# motor_42.net
KiCad netlist of a schematic drawn in Altium Designer
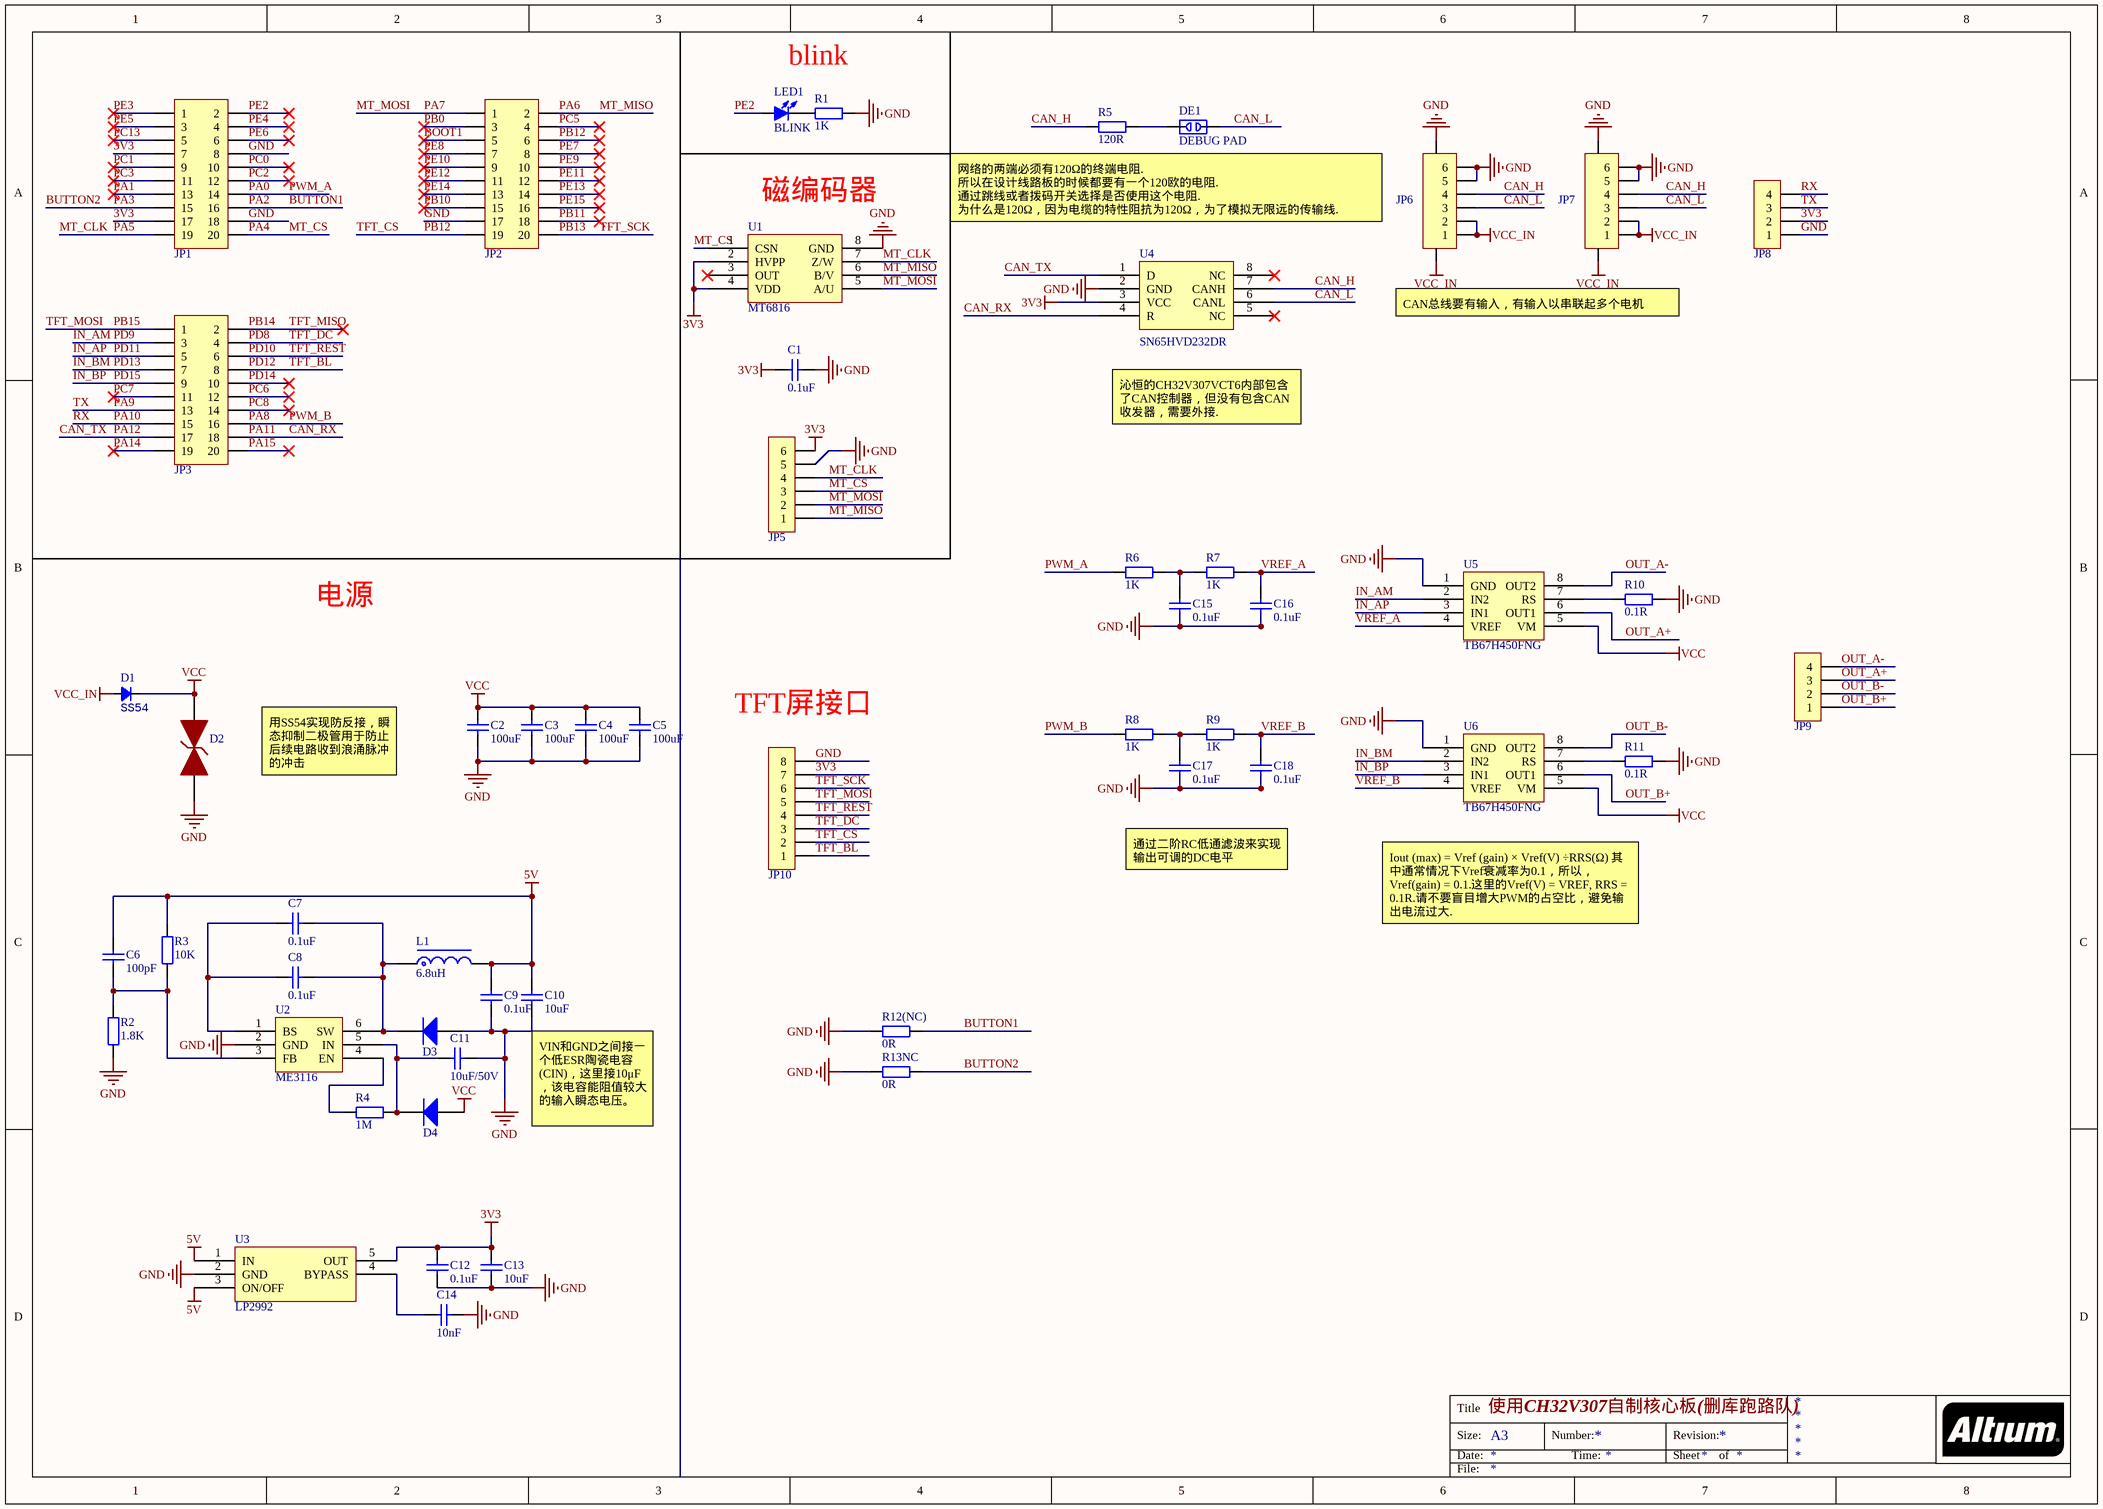
[diagram p0: motor_42.SchDoc]

(export (version "E")
  (design (tool "Eeschema 10.0.6"))
  (components
    (comp (ref "C1")
      (value "0.1uF")
      (footprint "C0805_L")
      (description "贴片电容/MLCC电容")
      (libsource (lib "0.1 - 电阻-电容-电感-晶振-晶体-磁珠-电位器-法拉电容-馈通电容") (part "C"))
    )
    (comp (ref "C2")
      (value "100uF")
      (footprint "C1206_L")
      (description "贴片电容/MLCC电容")
      (libsource (lib "0.1 - 电阻-电容-电感-晶振-晶体-磁珠-电位器-法拉电容-馈通电容") (part "C"))
    )
    (comp (ref "C3")
      (value "100uF")
      (footprint "C1206_L")
      (description "贴片电容/MLCC电容")
      (libsource (lib "0.1 - 电阻-电容-电感-晶振-晶体-磁珠-电位器-法拉电容-馈通电容") (part "C"))
    )
    (comp (ref "C4")
      (value "100uF")
      (footprint "C1206_L")
      (description "贴片电容/MLCC电容")
      (libsource (lib "0.1 - 电阻-电容-电感-晶振-晶体-磁珠-电位器-法拉电容-馈通电容") (part "C"))
    )
    (comp (ref "C5")
      (value "100uF")
      (footprint "C1206_L")
      (description "贴片电容/MLCC电容")
      (libsource (lib "0.1 - 电阻-电容-电感-晶振-晶体-磁珠-电位器-法拉电容-馈通电容") (part "C"))
    )
    (comp (ref "C6")
      (value "100pF")
      (footprint "C0402_L")
      (description "贴片电容/MLCC电容")
      (libsource (lib "0.1 - 电阻-电容-电感-晶振-晶体-磁珠-电位器-法拉电容-馈通电容") (part "C"))
    )
    (comp (ref "C7")
      (value "0.1uF")
      (footprint "C0402_L")
      (description "贴片电容/MLCC电容")
      (libsource (lib "0.1 - 电阻-电容-电感-晶振-晶体-磁珠-电位器-法拉电容-馈通电容") (part "C"))
    )
    (comp (ref "C8")
      (value "0.1uF")
      (footprint "C0402_L")
      (description "贴片电容/MLCC电容")
      (libsource (lib "0.1 - 电阻-电容-电感-晶振-晶体-磁珠-电位器-法拉电容-馈通电容") (part "C"))
    )
    (comp (ref "C9")
      (value "0.1uF")
      (footprint "C0402_L")
      (description "贴片电容/MLCC电容")
      (libsource (lib "0.1 - 电阻-电容-电感-晶振-晶体-磁珠-电位器-法拉电容-馈通电容") (part "C"))
    )
    (comp (ref "C10")
      (value "10uF")
      (footprint "C0402_L")
      (description "贴片电容/MLCC电容")
      (libsource (lib "0.1 - 电阻-电容-电感-晶振-晶体-磁珠-电位器-法拉电容-馈通电容") (part "C"))
    )
    (comp (ref "C11")
      (value "10uF/50V")
      (footprint "C0603_L")
      (description "陶瓷电容")
      (libsource (lib "0.1 - 电阻-电容-电感-晶振-晶体-磁珠-电位器-法拉电容-馈通电容") (part "C"))
    )
    (comp (ref "C12")
      (value "0.1uF")
      (footprint "C0402_L")
      (description "贴片电容/MLCC电容")
      (libsource (lib "0.1 - 电阻-电容-电感-晶振-晶体-磁珠-电位器-法拉电容-馈通电容") (part "C"))
    )
    (comp (ref "C13")
      (value "10uF")
      (footprint "C0402_L")
      (description "贴片电容/MLCC电容")
      (libsource (lib "0.1 - 电阻-电容-电感-晶振-晶体-磁珠-电位器-法拉电容-馈通电容") (part "C"))
    )
    (comp (ref "C14")
      (value "10nF")
      (footprint "C0402_L")
      (description "贴片电容/MLCC电容")
      (libsource (lib "0.1 - 电阻-电容-电感-晶振-晶体-磁珠-电位器-法拉电容-馈通电容") (part "C"))
    )
    (comp (ref "C15")
      (value "0.1uF")
      (footprint "C0402_L")
      (description "贴片电容/MLCC电容")
      (libsource (lib "0.1 - 电阻-电容-电感-晶振-晶体-磁珠-电位器-法拉电容-馈通电容") (part "C"))
    )
    (comp (ref "C16")
      (value "0.1uF")
      (footprint "C0402_L")
      (description "贴片电容/MLCC电容")
      (libsource (lib "0.1 - 电阻-电容-电感-晶振-晶体-磁珠-电位器-法拉电容-馈通电容") (part "C"))
    )
    (comp (ref "C17")
      (value "0.1uF")
      (footprint "C0402_L")
      (description "贴片电容/MLCC电容")
      (libsource (lib "0.1 - 电阻-电容-电感-晶振-晶体-磁珠-电位器-法拉电容-馈通电容") (part "C"))
    )
    (comp (ref "C18")
      (value "0.1uF")
      (footprint "C0402_L")
      (description "贴片电容/MLCC电容")
      (libsource (lib "0.1 - 电阻-电容-电感-晶振-晶体-磁珠-电位器-法拉电容-馈通电容") (part "C"))
    )
    (comp (ref "D1")
      (value "SS54")
      (footprint "SMA")
      (description "Diode")
      (libsource (lib "KitSprout") (part "Diode_SMA"))
    )
    (comp (ref "D2") (value "SMBJ28CA") (footprint "SMB") (libsource (lib "MyPcbLib") (part "SMBJ28CA")))
    (comp (ref "D3")
      (value "二极管-5819W")
      (footprint "SOD-323")
      (description "40V")
      (libsource (lib "0.2 - 二极管-TVS-ESD-整流桥-放电管") (part "二极管-5819W"))
    )
    (comp (ref "D4")
      (value "二极管-5819W")
      (footprint "SOD-323")
      (description "40V")
      (libsource (lib "0.2 - 二极管-TVS-ESD-整流桥-放电管") (part "二极管-5819W"))
    )
    (comp (ref "DE1")
      (value "DEBUG PAD")
      (footprint "DEBUG_A")
      (description "调试断点焊盘")
      (libsource (lib "0.5 - 按键_开关_蜂鸣器_保险丝_电池_测试点_Mark点_铜柱") (part "DEBUG"))
    )
    (comp (ref "JP1")
      (value "Header 2X10")
      (footprint "HDR2.54-LI-2x10P")
      (description "10*2P接插件")
      (libsource (lib "5.5 - 2.54mm连接器(KF2EDGK_XH2.54_2.54排针排母)") (part "Header 10X2"))
    )
    (comp (ref "JP2")
      (value "Header 2X10")
      (footprint "HDR2.54-LI-2x10P")
      (description "10*2P接插件")
      (libsource (lib "5.5 - 2.54mm连接器(KF2EDGK_XH2.54_2.54排针排母)") (part "Header 10X2"))
    )
    (comp (ref "JP3")
      (value "Header 2X10")
      (footprint "HDR2.54-LI-2x10P")
      (description "10*2P接插件")
      (libsource (lib "5.5 - 2.54mm连接器(KF2EDGK_XH2.54_2.54排针排母)") (part "Header 10X2"))
    )
    (comp (ref "JP5")
      (value "HDR-1X6")
      (footprint "HDR2.54-LI-6P")
      (description "6P接插件")
      (libsource (lib "5.5 - 2.54mm连接器(KF2EDGK_XH2.54_2.54排针排母)") (part "Header 6"))
    )
    (comp (ref "JP6")
      (value "HDR-1X6")
      (footprint "SH1.0-WT-6P")
      (description "6P连接器")
      (libsource (lib "5.0 - 1.00mm连接器(FPC1.0_SH1.0_1.0排针排母)") (part "Header 6"))
    )
    (comp (ref "JP7")
      (value "HDR-1X6")
      (footprint "SH1.0-WT-6P")
      (description "6P连接器")
      (libsource (lib "5.0 - 1.00mm连接器(FPC1.0_SH1.0_1.0排针排母)") (part "Header 6"))
    )
    (comp (ref "JP8")
      (value "HDR-1X4")
      (footprint "HDR2.54-LI-4P")
      (description "4P接插件")
      (libsource (lib "5.5 - 2.54mm连接器(KF2EDGK_XH2.54_2.54排针排母)") (part "Header 4"))
    )
    (comp (ref "JP9")
      (value "HDR-1X4")
      (footprint "XH2.54-LI-4P")
      (description "4P接插件")
      (libsource (lib "5.5 - 2.54mm连接器(KF2EDGK_XH2.54_2.54排针排母)") (part "Header 4"))
    )
    (comp (ref "JP10")
      (value "HDR-1X8")
      (footprint "HDR2.54-M-LI-8P")
      (description "8P接插件")
      (libsource (lib "5.5 - 2.54mm连接器(KF2EDGK_XH2.54_2.54排针排母)") (part "Header 8"))
    )
    (comp (ref "L1")
      (value "6.8uH")
      (footprint "L-SMD-0420")
      (description "一体成型电感")
      (libsource (lib "0.1 - 电阻-电容-电感-晶振-晶体-磁珠-电位器-法拉电容-馈通电容") (part "L-Molding Choke"))
    )
    (comp (ref "LED1")
      (value "BLINK")
      (footprint "LED0805_G")
      (description "贴片LED")
      (libsource (lib "0.3 - LED发光二极管-IR二极管_接收管-光耦") (part "LED-SMD"))
    )
    (comp (ref "R1")
      (value "1K")
      (footprint "R0402_L")
      (description "贴片电阻")
      (libsource (lib "0.1 - 电阻-电容-电感-晶振-晶体-磁珠-电位器-法拉电容-馈通电容") (part "R"))
    )
    (comp (ref "R2")
      (value "1.8K")
      (footprint "R0402_L")
      (description "贴片电阻")
      (libsource (lib "0.1 - 电阻-电容-电感-晶振-晶体-磁珠-电位器-法拉电容-馈通电容") (part "R"))
    )
    (comp (ref "R3")
      (value "10K")
      (footprint "R0402_L")
      (description "贴片电阻")
      (libsource (lib "0.1 - 电阻-电容-电感-晶振-晶体-磁珠-电位器-法拉电容-馈通电容") (part "R"))
    )
    (comp (ref "R4")
      (value "1M")
      (footprint "R0402_L")
      (description "贴片电阻")
      (libsource (lib "0.1 - 电阻-电容-电感-晶振-晶体-磁珠-电位器-法拉电容-馈通电容") (part "R"))
    )
    (comp (ref "R5")
      (value "120R")
      (footprint "R0402_L")
      (description "贴片电阻")
      (libsource (lib "0.1 - 电阻-电容-电感-晶振-晶体-磁珠-电位器-法拉电容-馈通电容") (part "R"))
    )
    (comp (ref "R6")
      (value "1K")
      (footprint "R0402_L")
      (description "贴片电阻")
      (libsource (lib "0.1 - 电阻-电容-电感-晶振-晶体-磁珠-电位器-法拉电容-馈通电容") (part "R"))
    )
    (comp (ref "R7")
      (value "1K")
      (footprint "R0402_L")
      (description "贴片电阻")
      (libsource (lib "0.1 - 电阻-电容-电感-晶振-晶体-磁珠-电位器-法拉电容-馈通电容") (part "R"))
    )
    (comp (ref "R8")
      (value "1K")
      (footprint "R0402_L")
      (description "贴片电阻")
      (libsource (lib "0.1 - 电阻-电容-电感-晶振-晶体-磁珠-电位器-法拉电容-馈通电容") (part "R"))
    )
    (comp (ref "R9")
      (value "1K")
      (footprint "R0402_L")
      (description "贴片电阻")
      (libsource (lib "0.1 - 电阻-电容-电感-晶振-晶体-磁珠-电位器-法拉电容-馈通电容") (part "R"))
    )
    (comp (ref "R10")
      (value "0.1R")
      (footprint "R1206_L")
      (description "贴片电阻")
      (libsource (lib "0.1 - 电阻-电容-电感-晶振-晶体-磁珠-电位器-法拉电容-馈通电容") (part "R"))
    )
    (comp (ref "R11")
      (value "0.1R")
      (footprint "R1206_L")
      (description "贴片电阻")
      (libsource (lib "0.1 - 电阻-电容-电感-晶振-晶体-磁珠-电位器-法拉电容-馈通电容") (part "R"))
    )
    (comp (ref "R12(NC)")
      (value "0R")
      (footprint "R0603_L")
      (description "贴片电阻")
      (libsource (lib "0.1 - 电阻-电容-电感-晶振-晶体-磁珠-电位器-法拉电容-馈通电容") (part "R"))
    )
    (comp (ref "R13NC")
      (value "0R")
      (footprint "R0603_L")
      (description "贴片电阻")
      (libsource (lib "0.1 - 电阻-电容-电感-晶振-晶体-磁珠-电位器-法拉电容-馈通电容") (part "R"))
    )
    (comp (ref "U1") (value "MT6816") (footprint "SOP8_L") (libsource (lib "MT6816") (part "MT6816")))
    (comp (ref "U2") (value "ME3116") (footprint "SOT23-6") (libsource (lib "MT6816") (part "ME3116")))
    (comp (ref "U3") (value "LP2992") (footprint "SOT23-5") (libsource (lib "MT6816") (part "LP2992")))
    (comp (ref "U4")
      (value "SN65HVD232D")
      (footprint "SOIC-8")
      (fields
        (field (name "MANUFACTURER") "Texas Instruments")
        (field (name "MANUFACTURER PART NUMBER") "SN65HVD232DR")
      )
      (libsource (lib "0.8 - 常见芯片") (part "SN65HVD232D"))
    )
    (comp (ref "U5")
      (value "TB67H450FNG")
      (footprint "HSOP-8")
      (libsource (lib "MT6816") (part "TB67H450FNG"))
    )
    (comp (ref "U6")
      (value "TB67H450FNG")
      (footprint "HSOP-8")
      (libsource (lib "MT6816") (part "TB67H450FNG"))
    )
  )
  (nets
    (net (code "1") (name "/BOOT1") (class "Default")
      (node (ref "JP2") (pin "5") (pinfunction "5_5") (pintype "passive+no_connect"))
    )
    (net (code "2") (name "/BUTTON1") (class "Default")
      (node (ref "JP1") (pin "16") (pinfunction "16_16") (pintype "passive"))
      (node (ref "R12(NC)") (pin "2") (pinfunction "2_2") (pintype "passive"))
    )
    (net (code "3") (name "/BUTTON2") (class "Default")
      (node (ref "JP1") (pin "15") (pinfunction "15_15") (pintype "passive"))
      (node (ref "R13NC") (pin "2") (pinfunction "2_2") (pintype "passive"))
    )
    (net (code "4") (name "/CAN_H") (class "Default")
      (node (ref "JP6") (pin "4") (pinfunction "4_4") (pintype "passive"))
      (node (ref "JP7") (pin "4") (pinfunction "4_4") (pintype "passive"))
      (node (ref "R5") (pin "1") (pinfunction "1_1") (pintype "passive"))
      (node (ref "U4") (pin "7") (pinfunction "CANH_7") (pintype "passive"))
    )
    (net (code "5") (name "/CAN_L") (class "Default")
      (node (ref "DE1") (pin "2") (pinfunction "2_2") (pintype "passive"))
      (node (ref "JP6") (pin "3") (pinfunction "3_3") (pintype "passive"))
      (node (ref "JP7") (pin "3") (pinfunction "3_3") (pintype "passive"))
      (node (ref "U4") (pin "6") (pinfunction "CANL_6") (pintype "passive"))
    )
    (net (code "6") (name "/CAN_RX") (class "Default")
      (node (ref "JP3") (pin "18") (pinfunction "18_18") (pintype "passive"))
      (node (ref "U4") (pin "4") (pinfunction "R_4") (pintype "passive"))
    )
    (net (code "7") (name "/CAN_TX") (class "Default")
      (node (ref "JP3") (pin "17") (pinfunction "17_17") (pintype "passive"))
      (node (ref "U4") (pin "1") (pinfunction "D_1") (pintype "passive"))
    )
    (net (code "8") (name "/IN_AM") (class "Default")
      (node (ref "JP3") (pin "3") (pinfunction "3_3") (pintype "passive"))
      (node (ref "U5") (pin "2") (pinfunction "IN2_2") (pintype "passive"))
    )
    (net (code "9") (name "/IN_AP") (class "Default")
      (node (ref "JP3") (pin "5") (pinfunction "5_5") (pintype "passive"))
      (node (ref "U5") (pin "3") (pinfunction "IN1_3") (pintype "passive"))
    )
    (net (code "10") (name "/IN_BM") (class "Default")
      (node (ref "JP3") (pin "7") (pinfunction "7_7") (pintype "passive"))
      (node (ref "U6") (pin "2") (pinfunction "IN2_2") (pintype "passive"))
    )
    (net (code "11") (name "/IN_BP") (class "Default")
      (node (ref "JP3") (pin "9") (pinfunction "9_9") (pintype "passive"))
      (node (ref "U6") (pin "3") (pinfunction "IN1_3") (pintype "passive"))
    )
    (net (code "12") (name "/MT_CLK") (class "Default")
      (node (ref "JP1") (pin "19") (pinfunction "19_19") (pintype "passive"))
      (node (ref "JP5") (pin "4") (pinfunction "4_4") (pintype "passive"))
      (node (ref "U1") (pin "7") (pinfunction "Z/W_7") (pintype "passive"))
    )
    (net (code "13") (name "/MT_CS") (class "Default")
      (node (ref "JP1") (pin "20") (pinfunction "20_20") (pintype "passive"))
      (node (ref "JP5") (pin "3") (pinfunction "3_3") (pintype "passive"))
      (node (ref "U1") (pin "1") (pinfunction "CSN_1") (pintype "passive"))
    )
    (net (code "14") (name "/MT_MISO") (class "Default")
      (node (ref "JP2") (pin "2") (pinfunction "2_2") (pintype "passive"))
      (node (ref "JP5") (pin "1") (pinfunction "1_1") (pintype "passive"))
      (node (ref "U1") (pin "6") (pinfunction "B/V_6") (pintype "passive"))
    )
    (net (code "15") (name "/MT_MOSI") (class "Default")
      (node (ref "JP2") (pin "1") (pinfunction "1_1") (pintype "passive"))
      (node (ref "JP5") (pin "2") (pinfunction "2_2") (pintype "passive"))
      (node (ref "U1") (pin "5") (pinfunction "A/U_5") (pintype "passive"))
    )
    (net (code "16") (name "/OUT_A+") (class "Default")
      (node (ref "JP9") (pin "3") (pinfunction "3_3") (pintype "passive"))
      (node (ref "U5") (pin "6") (pinfunction "OUT1_6") (pintype "passive"))
    )
    (net (code "17") (name "/OUT_A-") (class "Default")
      (node (ref "JP9") (pin "4") (pinfunction "4_4") (pintype "passive"))
      (node (ref "U5") (pin "8") (pinfunction "OUT2_8") (pintype "passive"))
    )
    (net (code "18") (name "/OUT_B+") (class "Default")
      (node (ref "JP9") (pin "1") (pinfunction "1_1") (pintype "passive"))
      (node (ref "U6") (pin "6") (pinfunction "OUT1_6") (pintype "passive"))
    )
    (net (code "19") (name "/OUT_B-") (class "Default")
      (node (ref "JP9") (pin "2") (pinfunction "2_2") (pintype "passive"))
      (node (ref "U6") (pin "8") (pinfunction "OUT2_8") (pintype "passive"))
    )
    (net (code "20") (name "/PA0") (class "Default")
      (node (ref "JP1") (pin "14") (pinfunction "14_14") (pintype "passive"))
      (node (ref "R6") (pin "1") (pinfunction "1_1") (pintype "passive"))
    )
    (net (code "21") (name "/PA1") (class "Default")
      (node (ref "JP1") (pin "13") (pinfunction "13_13") (pintype "passive+no_connect"))
    )
    (net (code "22") (name "/PA8") (class "Default")
      (node (ref "JP3") (pin "16") (pinfunction "16_16") (pintype "passive"))
      (node (ref "R8") (pin "1") (pinfunction "1_1") (pintype "passive"))
    )
    (net (code "23") (name "/PA9") (class "Default")
      (node (ref "JP3") (pin "13") (pinfunction "13_13") (pintype "passive"))
      (node (ref "JP8") (pin "3") (pinfunction "3_3") (pintype "passive"))
    )
    (net (code "24") (name "/PA10") (class "Default")
      (node (ref "JP3") (pin "15") (pinfunction "15_15") (pintype "passive"))
      (node (ref "JP8") (pin "4") (pinfunction "4_4") (pintype "passive"))
    )
    (net (code "25") (name "/PA14") (class "Default")
      (node (ref "JP3") (pin "19") (pinfunction "19_19") (pintype "passive+no_connect"))
    )
    (net (code "26") (name "/PA15") (class "Default")
      (node (ref "JP3") (pin "20") (pinfunction "20_20") (pintype "passive+no_connect"))
    )
    (net (code "27") (name "/PB0") (class "Default")
      (node (ref "JP2") (pin "3") (pinfunction "3_3") (pintype "passive+no_connect"))
    )
    (net (code "28") (name "/PB10") (class "Default")
      (node (ref "JP2") (pin "15") (pinfunction "15_15") (pintype "passive+no_connect"))
    )
    (net (code "29") (name "/PB11") (class "Default")
      (node (ref "JP2") (pin "18") (pinfunction "18_18") (pintype "passive+no_connect"))
    )
    (net (code "30") (name "/PB12") (class "Default")
      (node (ref "JP10") (pin "2") (pinfunction "2_2") (pintype "passive"))
      (node (ref "JP2") (pin "19") (pinfunction "19_19") (pintype "passive"))
      (node (ref "JP2") (pin "6") (pinfunction "6_6") (pintype "passive"))
    )
    (net (code "31") (name "/PB13") (class "Default")
      (node (ref "JP10") (pin "6") (pinfunction "6_6") (pintype "passive"))
      (node (ref "JP2") (pin "20") (pinfunction "20_20") (pintype "passive"))
    )
    (net (code "32") (name "/PB14") (class "Default")
      (node (ref "JP3") (pin "2") (pinfunction "2_2") (pintype "passive+no_connect"))
    )
    (net (code "33") (name "/PB15") (class "Default")
      (node (ref "JP10") (pin "5") (pinfunction "5_5") (pintype "passive"))
      (node (ref "JP3") (pin "1") (pinfunction "1_1") (pintype "passive"))
    )
    (net (code "34") (name "/PC0") (class "Default")
      (node (ref "JP1") (pin "10") (pinfunction "10_10") (pintype "passive+no_connect"))
    )
    (net (code "35") (name "/PC1") (class "Default")
      (node (ref "JP1") (pin "9") (pinfunction "9_9") (pintype "passive+no_connect"))
    )
    (net (code "36") (name "/PC2") (class "Default")
      (node (ref "JP1") (pin "12") (pinfunction "12_12") (pintype "passive+no_connect"))
    )
    (net (code "37") (name "/PC3") (class "Default")
      (node (ref "JP1") (pin "11") (pinfunction "11_11") (pintype "passive+no_connect"))
    )
    (net (code "38") (name "/PC5") (class "Default")
      (node (ref "JP2") (pin "4") (pinfunction "4_4") (pintype "passive+no_connect"))
    )
    (net (code "39") (name "/PC6") (class "Default")
      (node (ref "JP3") (pin "12") (pinfunction "12_12") (pintype "passive+no_connect"))
    )
    (net (code "40") (name "/PC7") (class "Default")
      (node (ref "JP3") (pin "11") (pinfunction "11_11") (pintype "passive+no_connect"))
    )
    (net (code "41") (name "/PC8") (class "Default")
      (node (ref "JP3") (pin "14") (pinfunction "14_14") (pintype "passive+no_connect"))
    )
    (net (code "42") (name "/PC13") (class "Default")
      (node (ref "JP1") (pin "5") (pinfunction "5_5") (pintype "passive+no_connect"))
    )
    (net (code "43") (name "/PD8") (class "Default")
      (node (ref "JP10") (pin "3") (pinfunction "3_3") (pintype "passive"))
      (node (ref "JP3") (pin "4") (pinfunction "4_4") (pintype "passive"))
    )
    (net (code "44") (name "/PD10") (class "Default")
      (node (ref "JP10") (pin "4") (pinfunction "4_4") (pintype "passive"))
      (node (ref "JP3") (pin "6") (pinfunction "6_6") (pintype "passive"))
    )
    (net (code "45") (name "/PD12") (class "Default")
      (node (ref "JP10") (pin "1") (pinfunction "1_1") (pintype "passive"))
      (node (ref "JP3") (pin "8") (pinfunction "8_8") (pintype "passive"))
    )
    (net (code "46") (name "/PD14") (class "Default")
      (node (ref "JP3") (pin "10") (pinfunction "10_10") (pintype "passive+no_connect"))
    )
    (net (code "47") (name "/PE2") (class "Default")
      (node (ref "JP1") (pin "2") (pinfunction "2_2") (pintype "passive"))
      (node (ref "LED1") (pin "1") (pinfunction "A_1") (pintype "passive"))
    )
    (net (code "48") (name "/PE3") (class "Default")
      (node (ref "JP1") (pin "1") (pinfunction "1_1") (pintype "passive+no_connect"))
    )
    (net (code "49") (name "/PE4") (class "Default")
      (node (ref "JP1") (pin "4") (pinfunction "4_4") (pintype "passive+no_connect"))
    )
    (net (code "50") (name "/PE5") (class "Default")
      (node (ref "JP1") (pin "3") (pinfunction "3_3") (pintype "passive+no_connect"))
    )
    (net (code "51") (name "/PE6") (class "Default")
      (node (ref "JP1") (pin "6") (pinfunction "6_6") (pintype "passive+no_connect"))
    )
    (net (code "52") (name "/PE7") (class "Default")
      (node (ref "JP2") (pin "8") (pinfunction "8_8") (pintype "passive+no_connect"))
    )
    (net (code "53") (name "/PE8") (class "Default")
      (node (ref "JP2") (pin "7") (pinfunction "7_7") (pintype "passive+no_connect"))
    )
    (net (code "54") (name "/PE9") (class "Default")
      (node (ref "JP2") (pin "10") (pinfunction "10_10") (pintype "passive+no_connect"))
    )
    (net (code "55") (name "/PE10") (class "Default")
      (node (ref "JP2") (pin "9") (pinfunction "9_9") (pintype "passive+no_connect"))
    )
    (net (code "56") (name "/PE11") (class "Default")
      (node (ref "JP2") (pin "12") (pinfunction "12_12") (pintype "passive+no_connect"))
    )
    (net (code "57") (name "/PE12") (class "Default")
      (node (ref "JP2") (pin "11") (pinfunction "11_11") (pintype "passive+no_connect"))
    )
    (net (code "58") (name "/PE13") (class "Default")
      (node (ref "JP2") (pin "14") (pinfunction "14_14") (pintype "passive+no_connect"))
    )
    (net (code "59") (name "/PE14") (class "Default")
      (node (ref "JP2") (pin "13") (pinfunction "13_13") (pintype "passive+no_connect"))
    )
    (net (code "60") (name "/PE15") (class "Default")
      (node (ref "JP2") (pin "16") (pinfunction "16_16") (pintype "passive+no_connect"))
    )
    (net (code "61") (name "/VREF_A") (class "Default")
      (node (ref "C16") (pin "2") (pinfunction "2_2") (pintype "passive"))
      (node (ref "R7") (pin "2") (pinfunction "2_2") (pintype "passive"))
      (node (ref "U5") (pin "4") (pinfunction "VREF_4") (pintype "passive"))
    )
    (net (code "62") (name "/VREF_B") (class "Default")
      (node (ref "C18") (pin "2") (pinfunction "2_2") (pintype "passive"))
      (node (ref "R9") (pin "2") (pinfunction "2_2") (pintype "passive"))
      (node (ref "U6") (pin "4") (pinfunction "VREF_4") (pintype "passive"))
    )
    (net (code "63") (name "3V3") (class "Default")
      (node (ref "C1") (pin "1") (pinfunction "1_1") (pintype "passive"))
      (node (ref "C12") (pin "2") (pinfunction "2_2") (pintype "passive"))
      (node (ref "C13") (pin "2") (pinfunction "2_2") (pintype "passive"))
      (node (ref "JP1") (pin "17") (pinfunction "17_17") (pintype "passive"))
      (node (ref "JP1") (pin "7") (pinfunction "7_7") (pintype "passive"))
      (node (ref "JP10") (pin "7") (pinfunction "7_7") (pintype "passive"))
      (node (ref "JP5") (pin "6") (pinfunction "6_6") (pintype "passive"))
      (node (ref "JP8") (pin "2") (pinfunction "2_2") (pintype "passive"))
      (node (ref "U1") (pin "2") (pinfunction "HVPP_2") (pintype "passive"))
      (node (ref "U1") (pin "4") (pinfunction "VDD_4") (pintype "passive"))
      (node (ref "U3") (pin "5") (pinfunction "OUT_5") (pintype "passive"))
      (node (ref "U4") (pin "3") (pinfunction "VCC_3") (pintype "passive"))
    )
    (net (code "64") (name "5V") (class "Default")
      (node (ref "C10") (pin "2") (pinfunction "2_2") (pintype "passive"))
      (node (ref "C6") (pin "2") (pinfunction "2_2") (pintype "passive"))
      (node (ref "C9") (pin "1") (pinfunction "1_1") (pintype "passive"))
      (node (ref "L1") (pin "2") (pinfunction "2_2") (pintype "passive"))
      (node (ref "R3") (pin "2") (pinfunction "2_2") (pintype "passive"))
      (node (ref "U3") (pin "1") (pinfunction "IN_1") (pintype "passive"))
      (node (ref "U3") (pin "3") (pinfunction "ON/OFF_3") (pintype "passive"))
    )
    (net (code "65") (name "GND") (class "Default")
      (node (ref "C1") (pin "2") (pinfunction "2_2") (pintype "passive"))
      (node (ref "C10") (pin "1") (pinfunction "1_1") (pintype "passive"))
      (node (ref "C11") (pin "1") (pinfunction "1_1") (pintype "passive"))
      (node (ref "C12") (pin "1") (pinfunction "1_1") (pintype "passive"))
      (node (ref "C13") (pin "1") (pinfunction "1_1") (pintype "passive"))
      (node (ref "C14") (pin "1") (pinfunction "1_1") (pintype "passive"))
      (node (ref "C15") (pin "1") (pinfunction "1_1") (pintype "passive"))
      (node (ref "C16") (pin "1") (pinfunction "1_1") (pintype "passive"))
      (node (ref "C17") (pin "1") (pinfunction "1_1") (pintype "passive"))
      (node (ref "C18") (pin "1") (pinfunction "1_1") (pintype "passive"))
      (node (ref "C2") (pin "1") (pinfunction "1_1") (pintype "passive"))
      (node (ref "C3") (pin "1") (pinfunction "1_1") (pintype "passive"))
      (node (ref "C4") (pin "1") (pinfunction "1_1") (pintype "passive"))
      (node (ref "C5") (pin "1") (pinfunction "1_1") (pintype "passive"))
      (node (ref "C9") (pin "2") (pinfunction "2_2") (pintype "passive"))
      (node (ref "D2") (pin "1") (pinfunction "1_1") (pintype "passive"))
      (node (ref "D3") (pin "1") (pinfunction "A_1") (pintype "passive"))
      (node (ref "JP1") (pin "18") (pinfunction "18_18") (pintype "passive"))
      (node (ref "JP1") (pin "8") (pinfunction "8_8") (pintype "passive"))
      (node (ref "JP10") (pin "8") (pinfunction "8_8") (pintype "passive"))
      (node (ref "JP2") (pin "17") (pinfunction "17_17") (pintype "passive"))
      (node (ref "JP5") (pin "5") (pinfunction "5_5") (pintype "passive"))
      (node (ref "JP6") (pin "0") (pinfunction "0_0") (pintype "passive"))
      (node (ref "JP6") (pin "5") (pinfunction "5_5") (pintype "passive"))
      (node (ref "JP6") (pin "6") (pinfunction "6_6") (pintype "passive"))
      (node (ref "JP7") (pin "0") (pinfunction "0_0") (pintype "passive"))
      (node (ref "JP7") (pin "5") (pinfunction "5_5") (pintype "passive"))
      (node (ref "JP7") (pin "6") (pinfunction "6_6") (pintype "passive"))
      (node (ref "JP8") (pin "1") (pinfunction "1_1") (pintype "passive"))
      (node (ref "R1") (pin "2") (pinfunction "2_2") (pintype "passive"))
      (node (ref "R10") (pin "2") (pinfunction "2_2") (pintype "passive"))
      (node (ref "R11") (pin "2") (pinfunction "2_2") (pintype "passive"))
      (node (ref "R12(NC)") (pin "1") (pinfunction "1_1") (pintype "passive"))
      (node (ref "R13NC") (pin "1") (pinfunction "1_1") (pintype "passive"))
      (node (ref "R2") (pin "1") (pinfunction "1_1") (pintype "passive"))
      (node (ref "U1") (pin "8") (pinfunction "GND_8") (pintype "passive"))
      (node (ref "U2") (pin "2") (pinfunction "GND_2") (pintype "passive"))
      (node (ref "U3") (pin "2") (pinfunction "GND_2") (pintype "passive"))
      (node (ref "U4") (pin "2") (pinfunction "GND_2") (pintype "passive"))
      (node (ref "U5") (pin "1") (pinfunction "GND_1") (pintype "passive"))
      (node (ref "U6") (pin "1") (pinfunction "GND_1") (pintype "passive"))
    )
    (net (code "66") (name "Net-(C15-Pad2)") (class "Default")
      (node (ref "C15") (pin "2") (pinfunction "2_2") (pintype "passive"))
      (node (ref "R6") (pin "2") (pinfunction "2_2") (pintype "passive"))
      (node (ref "R7") (pin "1") (pinfunction "1_1") (pintype "passive"))
    )
    (net (code "67") (name "Net-(C17-Pad2)") (class "Default")
      (node (ref "C17") (pin "2") (pinfunction "2_2") (pintype "passive"))
      (node (ref "R8") (pin "2") (pinfunction "2_2") (pintype "passive"))
      (node (ref "R9") (pin "1") (pinfunction "1_1") (pintype "passive"))
    )
    (net (code "68") (name "Net-(D3-K)") (class "Default")
      (node (ref "C7") (pin "1") (pinfunction "1_1") (pintype "passive"))
      (node (ref "C8") (pin "1") (pinfunction "1_1") (pintype "passive"))
      (node (ref "D3") (pin "2") (pinfunction "K_2") (pintype "passive"))
      (node (ref "L1") (pin "1") (pinfunction "1_1") (pintype "passive"))
      (node (ref "U2") (pin "6") (pinfunction "SW_6") (pintype "passive"))
    )
    (net (code "69") (name "Net-(D4-K)") (class "Default")
      (node (ref "C11") (pin "2") (pinfunction "2_2") (pintype "passive"))
      (node (ref "D4") (pin "2") (pinfunction "K_2") (pintype "passive"))
      (node (ref "R4") (pin "2") (pinfunction "2_2") (pintype "passive"))
      (node (ref "U2") (pin "5") (pinfunction "IN_5") (pintype "passive"))
    )
    (net (code "70") (name "Net-(DE1-Pad1)") (class "Default")
      (node (ref "DE1") (pin "1") (pinfunction "1_1") (pintype "passive"))
      (node (ref "R5") (pin "2") (pinfunction "2_2") (pintype "passive"))
    )
    (net (code "71") (name "Net-(LED1-K)") (class "Default")
      (node (ref "LED1") (pin "2") (pinfunction "K_2") (pintype "passive"))
      (node (ref "R1") (pin "1") (pinfunction "1_1") (pintype "passive"))
    )
    (net (code "72") (name "Net-(U2-BS)") (class "Default")
      (node (ref "C7") (pin "2") (pinfunction "2_2") (pintype "passive"))
      (node (ref "C8") (pin "2") (pinfunction "2_2") (pintype "passive"))
      (node (ref "U2") (pin "1") (pinfunction "BS_1") (pintype "passive"))
    )
    (net (code "73") (name "Net-(U2-EN)") (class "Default")
      (node (ref "R4") (pin "1") (pinfunction "1_1") (pintype "passive"))
      (node (ref "U2") (pin "4") (pinfunction "EN_4") (pintype "passive"))
    )
    (net (code "74") (name "Net-(U2-FB)") (class "Default")
      (node (ref "C6") (pin "1") (pinfunction "1_1") (pintype "passive"))
      (node (ref "R2") (pin "2") (pinfunction "2_2") (pintype "passive"))
      (node (ref "R3") (pin "1") (pinfunction "1_1") (pintype "passive"))
      (node (ref "U2") (pin "3") (pinfunction "FB_3") (pintype "passive"))
    )
    (net (code "75") (name "Net-(U3-BYPASS)") (class "Default")
      (node (ref "C14") (pin "2") (pinfunction "2_2") (pintype "passive"))
      (node (ref "U3") (pin "4") (pinfunction "BYPASS_4") (pintype "passive"))
    )
    (net (code "76") (name "Net-(U5-RS)") (class "Default")
      (node (ref "R10") (pin "1") (pinfunction "1_1") (pintype "passive"))
      (node (ref "U5") (pin "7") (pinfunction "RS_7") (pintype "passive"))
    )
    (net (code "77") (name "Net-(U6-RS)") (class "Default")
      (node (ref "R11") (pin "1") (pinfunction "1_1") (pintype "passive"))
      (node (ref "U6") (pin "7") (pinfunction "RS_7") (pintype "passive"))
    )
    (net (code "78") (name "VCC") (class "Default")
      (node (ref "C2") (pin "2") (pinfunction "2_2") (pintype "passive"))
      (node (ref "C3") (pin "2") (pinfunction "2_2") (pintype "passive"))
      (node (ref "C4") (pin "2") (pinfunction "2_2") (pintype "passive"))
      (node (ref "C5") (pin "2") (pinfunction "2_2") (pintype "passive"))
      (node (ref "D1") (pin "2") (pinfunction "K_2") (pintype "passive"))
      (node (ref "D2") (pin "2") (pinfunction "2_2") (pintype "passive"))
      (node (ref "D4") (pin "1") (pinfunction "A_1") (pintype "passive"))
      (node (ref "U5") (pin "5") (pinfunction "VM_5") (pintype "passive"))
      (node (ref "U6") (pin "5") (pinfunction "VM_5") (pintype "passive"))
    )
    (net (code "79") (name "VCC_IN") (class "Default")
      (node (ref "D1") (pin "1") (pinfunction "A_1") (pintype "passive"))
      (node (ref "JP6") (pin "0") (pinfunction "0_0") (pintype "passive"))
      (node (ref "JP6") (pin "1") (pinfunction "1_1") (pintype "passive"))
      (node (ref "JP6") (pin "2") (pinfunction "2_2") (pintype "passive"))
      (node (ref "JP7") (pin "0") (pinfunction "0_0") (pintype "passive"))
      (node (ref "JP7") (pin "1") (pinfunction "1_1") (pintype "passive"))
      (node (ref "JP7") (pin "2") (pinfunction "2_2") (pintype "passive"))
    )
    (net (code "80") (name "unconnected-(U1-OUT-Pad3)") (class "Default")
      (node (ref "U1") (pin "3") (pinfunction "OUT_3") (pintype "passive+no_connect"))
    )
    (net (code "81") (name "unconnected-(U4-NC-Pad5)") (class "Default")
      (node (ref "U4") (pin "5") (pinfunction "NC_5") (pintype "passive+no_connect"))
    )
    (net (code "82") (name "unconnected-(U4-NC-Pad8)") (class "Default")
      (node (ref "U4") (pin "8") (pinfunction "NC_8") (pintype "passive+no_connect"))
    )
  )
)
